# design.net
KiCad netlist of a schematic drawn in Altium Designer
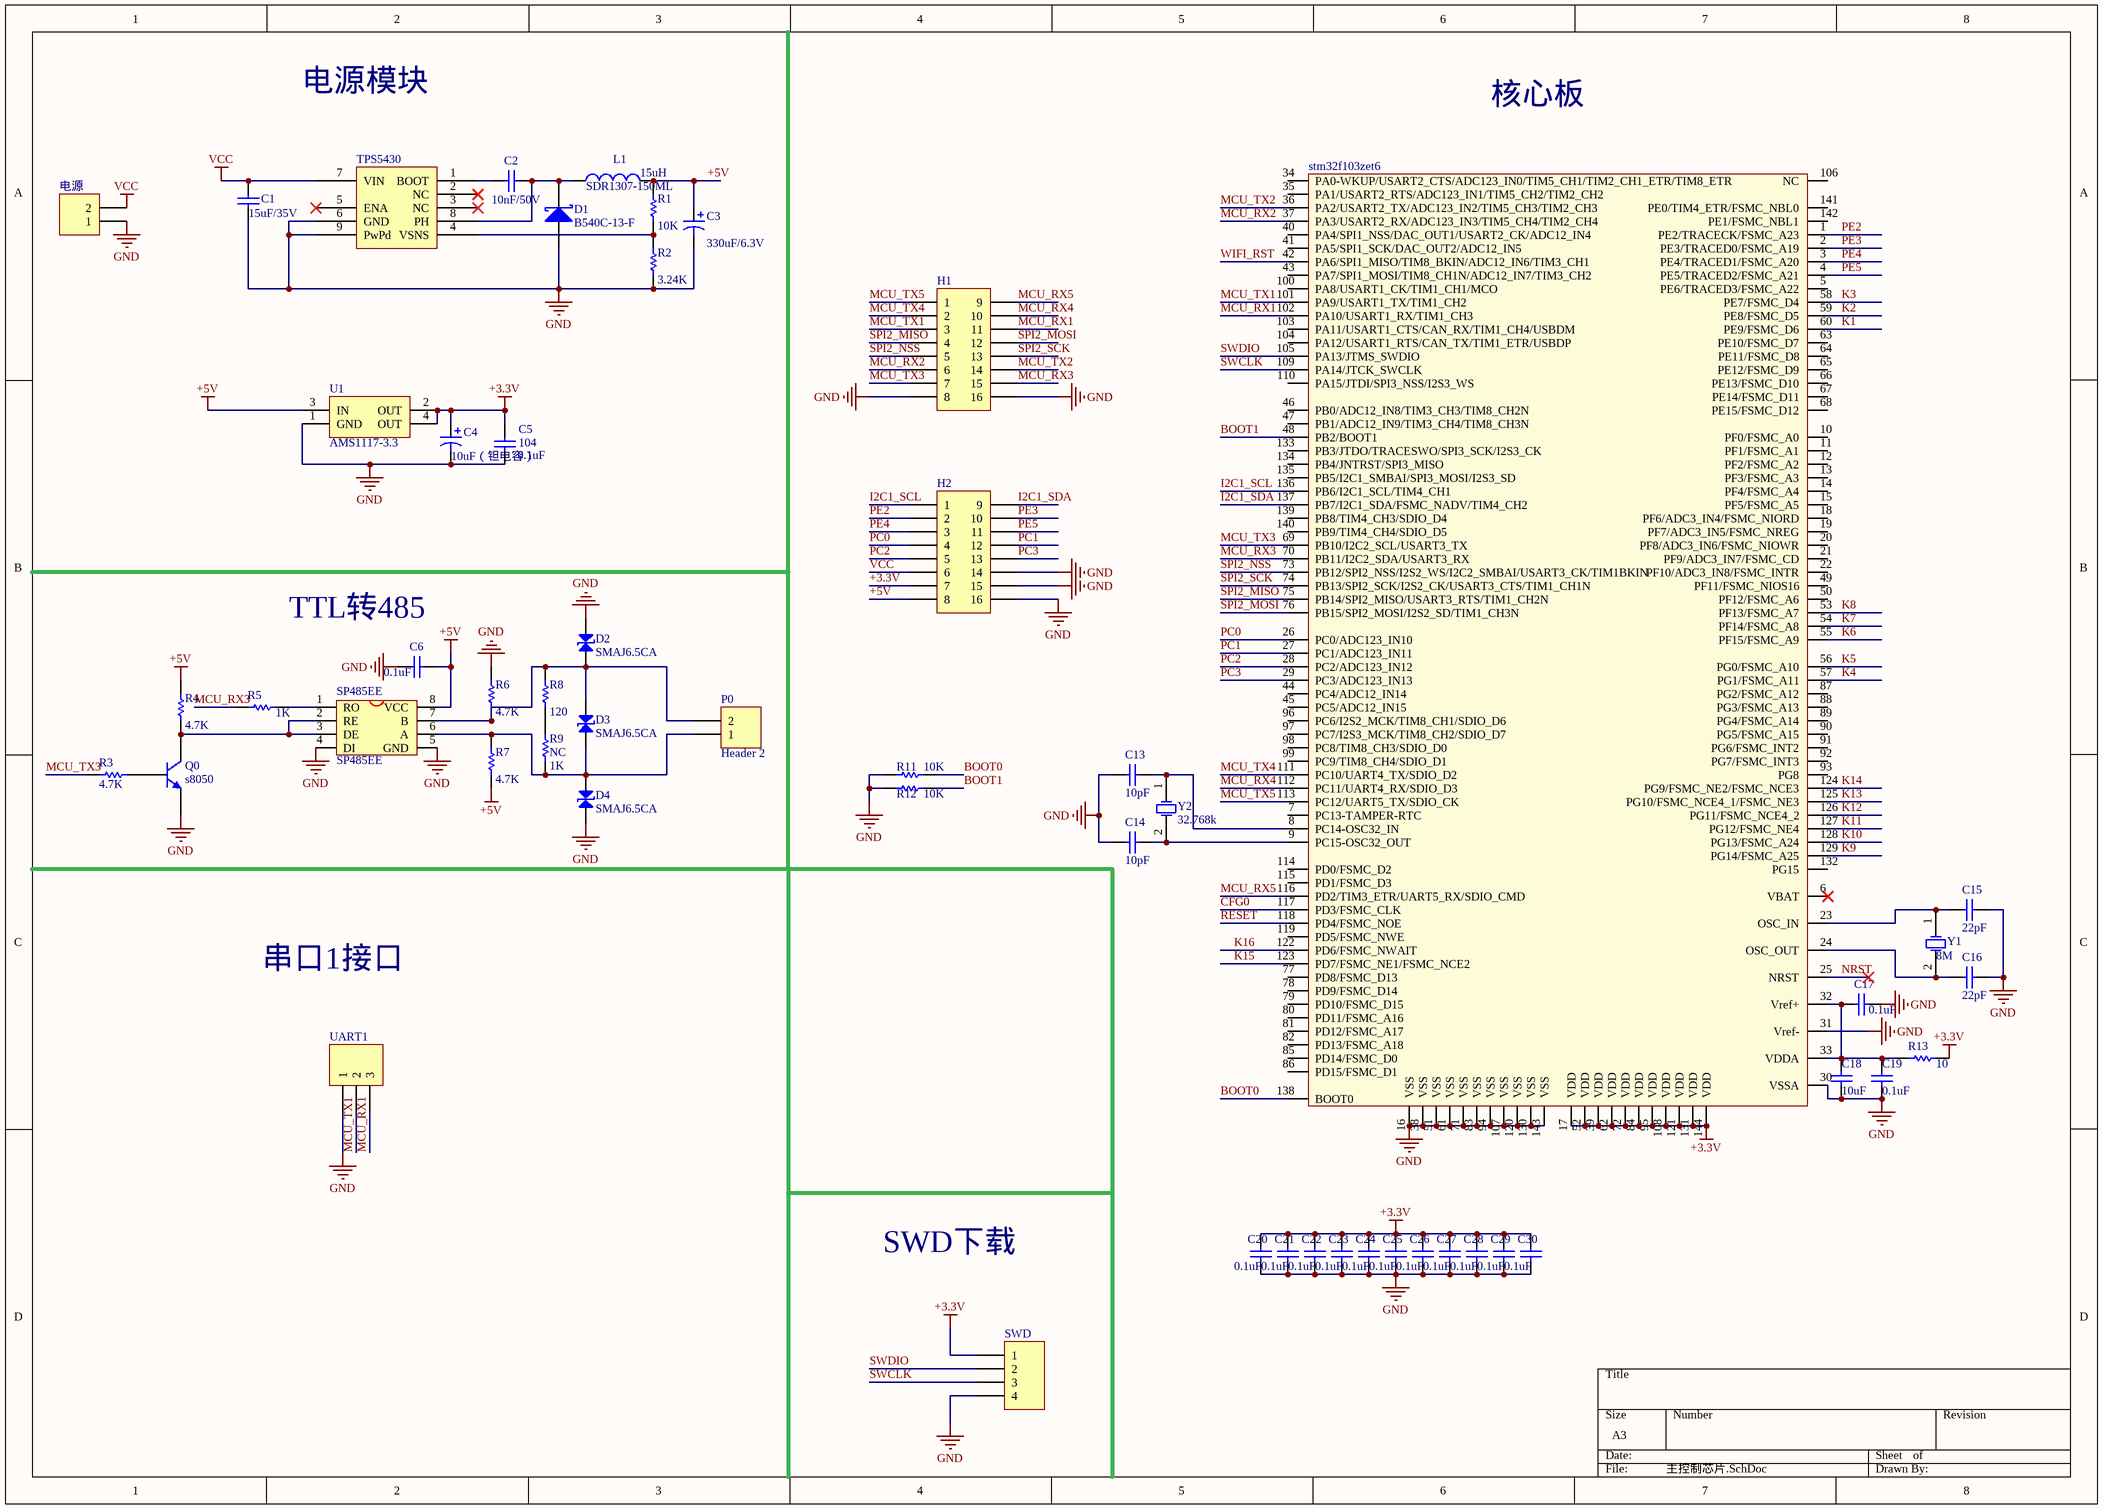
[diagram p0: 主控制芯片.SchDoc]

(export (version "E")
  (design (tool "Eeschema 10.0.6"))
  (components
    (comp (ref "C1")
      (value "15uF/35V")
      (footprint "1206")
      (description "Capacitor")
      (fields (field (name "Comment") "C2012X5R1V156M125AC") (field (name "PUBLISHER") "Altium Limited"))
      (libsource (lib "Miscellaneous Devices") (part "Cap"))
    )
    (comp (ref "C2")
      (value "10nF/50V")
      (footprint "0603")
      (description "Capacitor")
      (fields (field (name "Comment") "C0805C103K5RACTU") (field (name "PUBLISHER") "Altium Limited"))
      (libsource (lib "Miscellaneous Devices") (part "Cap"))
    )
    (comp (ref "C3")
      (value "330uF/6.3V")
      (footprint "钽电容(D)")
      (description "Polarized Capacitor (Radial)")
      (fields (field (name "Comment") "6TPC330MA") (field (name "PUBLISHER") "Altium Limited"))
      (libsource (lib "Miscellaneous Devices") (part "Cap Pol1"))
    )
    (comp (ref "C4")
      (value "10uF（钽电容）")
      (footprint "钽电容(B)")
      (description "Polarized Capacitor (Radial)")
      (fields (field (name "PUBLISHER") "Altium Limited"))
      (libsource (lib "Miscellaneous Devices") (part "Cap Pol1"))
    )
    (comp (ref "C5")
      (value "104")
      (footprint "0603")
      (description "Capacitor")
      (fields (field (name "ALTIUM_VALUE") "0.1uF") (field (name "PUBLISHER") "Altium Limited"))
      (libsource (lib "Miscellaneous Devices") (part "Cap"))
    )
    (comp (ref "C6")
      (value "0.1uF")
      (footprint "0603")
      (description "Capacitor")
      (fields (field (name "Comment") "104") (field (name "PUBLISHER") "Altium Limited"))
      (libsource (lib "Miscellaneous Devices") (part "Cap"))
    )
    (comp (ref "C13")
      (value "10pF")
      (footprint "0603")
      (description "Capacitor")
      (fields (field (name "Comment") "10") (field (name "PUBLISHER") "Altium Limited"))
      (libsource (lib "Miscellaneous Devices") (part "Cap"))
    )
    (comp (ref "C14")
      (value "10pF")
      (footprint "0603")
      (description "Capacitor")
      (fields (field (name "Comment") "10") (field (name "PUBLISHER") "Altium Limited"))
      (libsource (lib "Miscellaneous Devices") (part "Cap"))
    )
    (comp (ref "C15")
      (value "22pF")
      (footprint "0603")
      (description "Capacitor")
      (fields (field (name "Comment") "22") (field (name "PUBLISHER") "Altium Limited"))
      (libsource (lib "Miscellaneous Devices") (part "Cap"))
    )
    (comp (ref "C16")
      (value "22pF")
      (footprint "0603")
      (description "Capacitor")
      (fields (field (name "Comment") "22") (field (name "PUBLISHER") "Altium Limited"))
      (libsource (lib "Miscellaneous Devices") (part "Cap"))
    )
    (comp (ref "C17")
      (value "0.1uF")
      (footprint "0603")
      (description "Capacitor")
      (fields (field (name "Comment") "104") (field (name "PUBLISHER") "Altium Limited"))
      (libsource (lib "Miscellaneous Devices") (part "Cap"))
    )
    (comp (ref "C18")
      (value "10uF")
      (footprint "0603")
      (description "Capacitor")
      (fields (field (name "Comment") "106") (field (name "PUBLISHER") "Altium Limited"))
      (libsource (lib "Miscellaneous Devices") (part "Cap"))
    )
    (comp (ref "C19")
      (value "0.1uF")
      (footprint "0603")
      (description "Capacitor")
      (fields (field (name "Comment") "104") (field (name "PUBLISHER") "Altium Limited"))
      (libsource (lib "Miscellaneous Devices") (part "Cap"))
    )
    (comp (ref "C20")
      (value "0.1uF")
      (footprint "0603")
      (description "Capacitor")
      (fields (field (name "Comment") "104") (field (name "PUBLISHER") "Altium Limited"))
      (libsource (lib "Miscellaneous Devices") (part "Cap"))
    )
    (comp (ref "C21")
      (value "0.1uF")
      (footprint "0603")
      (description "Capacitor")
      (fields (field (name "Comment") "104") (field (name "PUBLISHER") "Altium Limited"))
      (libsource (lib "Miscellaneous Devices") (part "Cap"))
    )
    (comp (ref "C22")
      (value "0.1uF")
      (footprint "0603")
      (description "Capacitor")
      (fields (field (name "Comment") "104") (field (name "PUBLISHER") "Altium Limited"))
      (libsource (lib "Miscellaneous Devices") (part "Cap"))
    )
    (comp (ref "C23")
      (value "0.1uF")
      (footprint "0603")
      (description "Capacitor")
      (fields (field (name "Comment") "104") (field (name "PUBLISHER") "Altium Limited"))
      (libsource (lib "Miscellaneous Devices") (part "Cap"))
    )
    (comp (ref "C24")
      (value "0.1uF")
      (footprint "0603")
      (description "Capacitor")
      (fields (field (name "Comment") "104") (field (name "PUBLISHER") "Altium Limited"))
      (libsource (lib "Miscellaneous Devices") (part "Cap"))
    )
    (comp (ref "C25")
      (value "0.1uF")
      (footprint "0603")
      (description "Capacitor")
      (fields (field (name "Comment") "104") (field (name "PUBLISHER") "Altium Limited"))
      (libsource (lib "Miscellaneous Devices") (part "Cap"))
    )
    (comp (ref "C26")
      (value "0.1uF")
      (footprint "0603")
      (description "Capacitor")
      (fields (field (name "Comment") "104") (field (name "PUBLISHER") "Altium Limited"))
      (libsource (lib "Miscellaneous Devices") (part "Cap"))
    )
    (comp (ref "C27")
      (value "0.1uF")
      (footprint "0603")
      (description "Capacitor")
      (fields (field (name "Comment") "104") (field (name "PUBLISHER") "Altium Limited"))
      (libsource (lib "Miscellaneous Devices") (part "Cap"))
    )
    (comp (ref "C28")
      (value "0.1uF")
      (footprint "0603")
      (description "Capacitor")
      (fields (field (name "Comment") "104") (field (name "PUBLISHER") "Altium Limited"))
      (libsource (lib "Miscellaneous Devices") (part "Cap"))
    )
    (comp (ref "C29")
      (value "0.1uF")
      (footprint "0603")
      (description "Capacitor")
      (fields (field (name "Comment") "104") (field (name "PUBLISHER") "Altium Limited"))
      (libsource (lib "Miscellaneous Devices") (part "Cap"))
    )
    (comp (ref "C30")
      (value "0.1uF")
      (footprint "0603")
      (description "Capacitor")
      (fields (field (name "Comment") "104") (field (name "PUBLISHER") "Altium Limited"))
      (libsource (lib "Miscellaneous Devices") (part "Cap"))
    )
    (comp (ref "D1")
      (value "B540C-13-F")
      (footprint "SMC")
      (description "Schottky Diode")
      (fields (field (name "PUBLISHER") "Altium Limited"))
      (libsource (lib "Miscellaneous Devices") (part "D Schottky"))
    )
    (comp (ref "D2") (value "SMAJ6.5CA") (footprint "SMA") (libsource (lib "智能柜") (part "MSCJ6.5CA")))
    (comp (ref "D3") (value "SMAJ6.5CA") (footprint "SMA") (libsource (lib "智能柜") (part "MSCJ6.5CA")))
    (comp (ref "D4") (value "SMAJ6.5CA") (footprint "SMA") (libsource (lib "智能柜") (part "MSCJ6.5CA")))
    (comp (ref "H1")
      (value "Header 8X2A")
      (footprint "HDR2X8_CEN")
      (description "Header, 8-Pin, Dual row")
      (fields (field (name "PUBLISHER") "Altium Limited"))
      (libsource (lib "Miscellaneous Connectors") (part "Header 8X2A"))
    )
    (comp (ref "H2")
      (value "Header 8X2A")
      (footprint "HDR2X8_CEN")
      (description "Header, 8-Pin, Dual row")
      (fields (field (name "PUBLISHER") "Altium Limited"))
      (libsource (lib "Miscellaneous Connectors") (part "Header 8X2A"))
    )
    (comp (ref "L1")
      (value "SDR1307-150ML")
      (footprint "CDRH127")
      (description "Inductor")
      (fields (field (name "ALTIUM_VALUE") "15uH") (field (name "PUBLISHER") "Altium Limited"))
      (libsource (lib "Miscellaneous Devices") (part "Inductor"))
    )
    (comp (ref "P0")
      (value "Header 2")
      (footprint "电源")
      (description "Header, 2-Pin")
      (fields (field (name "PUBLISHER") "Altium Limited"))
      (libsource (lib "") (part "Header 2_1"))
    )
    (comp (ref "Q0")
      (value "s8050")
      (footprint "SOT-23")
      (description "NPN Bipolar Transistor")
      (fields (field (name "PUBLISHER") "Altium Limited"))
      (libsource (lib "Miscellaneous Devices") (part "NPN"))
    )
    (comp (ref "R1")
      (value "10K")
      (footprint "0603")
      (description "Resistor")
      (fields (field (name "PUBLISHER") "Altium Limited"))
      (libsource (lib "Miscellaneous Devices") (part "Res1"))
    )
    (comp (ref "R2")
      (value "3.24K")
      (footprint "0603")
      (description "Resistor")
      (fields (field (name "PUBLISHER") "Altium Limited"))
      (libsource (lib "Miscellaneous Devices") (part "Res1"))
    )
    (comp (ref "R3")
      (value "4.7K")
      (footprint "0603")
      (description "Resistor")
      (fields (field (name "Comment") "4.7k") (field (name "PUBLISHER") "Altium Limited"))
      (libsource (lib "Miscellaneous Devices") (part "Res1"))
    )
    (comp (ref "R4")
      (value "4.7K")
      (footprint "0603")
      (description "Resistor")
      (fields (field (name "Comment") "4.7k") (field (name "PUBLISHER") "Altium Limited"))
      (libsource (lib "Miscellaneous Devices") (part "Res1"))
    )
    (comp (ref "R5")
      (value "1K")
      (footprint "0603")
      (description "Resistor")
      (fields (field (name "PUBLISHER") "Altium Limited"))
      (libsource (lib "Miscellaneous Devices") (part "Res1"))
    )
    (comp (ref "R6")
      (value "4.7K")
      (footprint "0603")
      (description "Resistor")
      (fields (field (name "Comment") "4.7k") (field (name "PUBLISHER") "Altium Limited"))
      (libsource (lib "Miscellaneous Devices") (part "Res1"))
    )
    (comp (ref "R7")
      (value "4.7K")
      (footprint "0603")
      (description "Resistor")
      (fields (field (name "Comment") "4.7k") (field (name "PUBLISHER") "Altium Limited"))
      (libsource (lib "Miscellaneous Devices") (part "Res1"))
    )
    (comp (ref "R8")
      (value "120")
      (footprint "0603")
      (description "Resistor")
      (fields (field (name "PUBLISHER") "Altium Limited"))
      (libsource (lib "Miscellaneous Devices") (part "Res1"))
    )
    (comp (ref "R9")
      (value "NC")
      (footprint "0603")
      (description "Resistor")
      (fields (field (name "ALTIUM_VALUE") "1K") (field (name "PUBLISHER") "Altium Limited"))
      (libsource (lib "Miscellaneous Devices") (part "Res1"))
    )
    (comp (ref "R11")
      (value "10K")
      (footprint "0603")
      (description "Resistor")
      (fields (field (name "PUBLISHER") "Altium Limited"))
      (libsource (lib "Miscellaneous Devices") (part "Res1"))
    )
    (comp (ref "R12")
      (value "10K")
      (footprint "0603")
      (description "Resistor")
      (fields (field (name "PUBLISHER") "Altium Limited"))
      (libsource (lib "Miscellaneous Devices") (part "Res1"))
    )
    (comp (ref "R13")
      (value "10")
      (footprint "0603")
      (description "Resistor")
      (fields (field (name "PUBLISHER") "Altium Limited"))
      (libsource (lib "Miscellaneous Devices") (part "Res1"))
    )
    (comp (ref "SP485EE") (value "SP485EE") (footprint "SOP-8") (libsource (lib "智能柜") (part "SP485EE")))
    (comp (ref "stm32f103zet6")
      (value "stm32f103zet6")
      (footprint "LQFP144")
      (libsource (lib "智能柜") (part "stm32f103zet6"))
    )
    (comp (ref "SWD")
      (value "Header 4")
      (footprint "SWD")
      (description "Header, 4-Pin")
      (fields (field (name "PUBLISHER") "Altium Limited"))
      (libsource (lib "Miscellaneous Connectors") (part "Header 4"))
    )
    (comp (ref "TPS5430")
      (value "TPS5430DDAR")
      (footprint "TPS5430")
      (libsource (lib "Schlib1") (part "TPS5430"))
    )
    (comp (ref "U1")
      (value "AMS1117-3.3")
      (footprint "1117-3.3")
      (description "800mA and 1A Low Dropout Positive Regulator 2.85V, 3.3V, 5V, and Adjustable")
      (fields (field (name "PUBLISHER") "Altium Limited"))
      (libsource (lib "BB Power Mgt Voltage Regulator") (part "REG1117-3.3"))
    )
    (comp (ref "UART1")
      (value "Header 3")
      (footprint "H3")
      (description "Header, 3-Pin")
      (fields (field (name "PUBLISHER") "Altium Limited"))
      (libsource (lib "Miscellaneous Connectors") (part "Header 3"))
    )
    (comp (ref "Y1")
      (value "8M")
      (footprint "5032(8M)")
      (description "Crystal Oscillator")
      (fields (field (name "PUBLISHER") "Altium Limited"))
      (libsource (lib "Miscellaneous Devices") (part "XTAL"))
    )
    (comp (ref "Y2")
      (value "32.768k")
      (footprint "FC135(32.768K)")
      (description "Crystal Oscillator")
      (fields (field (name "PUBLISHER") "Altium Limited"))
      (libsource (lib "Miscellaneous Devices") (part "XTAL"))
    )
    (comp (ref "电源")
      (value "DUANZI")
      (footprint "电源")
      (description "Header, 2-Pin")
      (fields (field (name "PUBLISHER") "Altium Limited"))
      (libsource (lib "Miscellaneous Connectors") (part "Header 2"))
    )
  )
  (nets
    (net (code "1") (name "+3.3V") (class "Default")
      (node (ref "C20") (pin "1") (pinfunction "1_1") (pintype "passive"))
      (node (ref "C21") (pin "1") (pinfunction "1_1") (pintype "passive"))
      (node (ref "C22") (pin "1") (pinfunction "1_1") (pintype "passive"))
      (node (ref "C23") (pin "1") (pinfunction "1_1") (pintype "passive"))
      (node (ref "C24") (pin "1") (pinfunction "1_1") (pintype "passive"))
      (node (ref "C25") (pin "1") (pinfunction "1_1") (pintype "passive"))
      (node (ref "C26") (pin "1") (pinfunction "1_1") (pintype "passive"))
      (node (ref "C27") (pin "1") (pinfunction "1_1") (pintype "passive"))
      (node (ref "C28") (pin "1") (pinfunction "1_1") (pintype "passive"))
      (node (ref "C29") (pin "1") (pinfunction "1_1") (pintype "passive"))
      (node (ref "C30") (pin "1") (pinfunction "1_1") (pintype "passive"))
      (node (ref "C4") (pin "1") (pinfunction "1_1") (pintype "passive"))
      (node (ref "C5") (pin "2") (pinfunction "2_2") (pintype "passive"))
      (node (ref "H2") (pin "7") (pinfunction "7_7") (pintype "passive"))
      (node (ref "R13") (pin "2") (pinfunction "2_2") (pintype "passive"))
      (node (ref "SWD") (pin "1") (pinfunction "1_1") (pintype "passive"))
      (node (ref "U1") (pin "2") (pinfunction "OUT_2") (pintype "power_in"))
      (node (ref "U1") (pin "4") (pinfunction "OUT_4") (pintype "power_in"))
      (node (ref "stm32f103zet6") (pin "108") (pinfunction "VDD_108") (pintype "passive"))
      (node (ref "stm32f103zet6") (pin "121") (pinfunction "VDD_121") (pintype "passive"))
      (node (ref "stm32f103zet6") (pin "131") (pinfunction "VDD_131") (pintype "passive"))
      (node (ref "stm32f103zet6") (pin "144") (pinfunction "VDD_144") (pintype "passive"))
      (node (ref "stm32f103zet6") (pin "17") (pinfunction "VDD_17") (pintype "passive"))
      (node (ref "stm32f103zet6") (pin "39") (pinfunction "VDD_39") (pintype "passive"))
      (node (ref "stm32f103zet6") (pin "52") (pinfunction "VDD_52") (pintype "passive"))
      (node (ref "stm32f103zet6") (pin "62") (pinfunction "VDD_62") (pintype "passive"))
      (node (ref "stm32f103zet6") (pin "72") (pinfunction "VDD_72") (pintype "passive"))
      (node (ref "stm32f103zet6") (pin "84") (pinfunction "VDD_84") (pintype "passive"))
      (node (ref "stm32f103zet6") (pin "95") (pinfunction "VDD_95") (pintype "passive"))
    )
    (net (code "2") (name "+5V") (class "Default")
      (node (ref "C3") (pin "1") (pinfunction "1_1") (pintype "passive"))
      (node (ref "C6") (pin "2") (pinfunction "2_2") (pintype "passive"))
      (node (ref "H2") (pin "8") (pinfunction "8_8") (pintype "passive"))
      (node (ref "L1") (pin "2") (pinfunction "2_2") (pintype "passive"))
      (node (ref "R1") (pin "2") (pinfunction "2_2") (pintype "passive"))
      (node (ref "R4") (pin "1") (pinfunction "1_1") (pintype "passive"))
      (node (ref "R7") (pin "2") (pinfunction "2_2") (pintype "passive"))
      (node (ref "SP485EE") (pin "8") (pinfunction "VCC_8") (pintype "passive"))
      (node (ref "U1") (pin "3") (pinfunction "IN_3") (pintype "power_in"))
    )
    (net (code "3") (name "/BOOT0") (class "Default")
      (node (ref "R11") (pin "1") (pinfunction "1_1") (pintype "passive"))
      (node (ref "stm32f103zet6") (pin "138") (pinfunction "BOOT0_138") (pintype "passive"))
    )
    (net (code "4") (name "/BOOT1") (class "Default")
      (node (ref "R12") (pin "1") (pinfunction "1_1") (pintype "passive"))
      (node (ref "stm32f103zet6") (pin "48") (pinfunction "PB2/BOOT1_48") (pintype "passive"))
    )
    (net (code "5") (name "/CFG0") (class "Default")
      (node (ref "stm32f103zet6") (pin "117") (pinfunction "PD3/FSMC_CLK_117") (pintype "passive"))
    )
    (net (code "6") (name "/I2C1_SCL") (class "Default")
      (node (ref "H2") (pin "1") (pinfunction "1_1") (pintype "passive"))
      (node (ref "stm32f103zet6") (pin "136") (pinfunction "PB6/I2C1_SCL/TIM4_CH1_136") (pintype "passive"))
    )
    (net (code "7") (name "/I2C1_SDA") (class "Default")
      (node (ref "H2") (pin "9") (pinfunction "9_9") (pintype "passive"))
      (node (ref "stm32f103zet6") (pin "137") (pinfunction "PB7/I2C1_SDA/FSMC_NADV/TIM4_CH2_137") (pintype "passive"))
    )
    (net (code "8") (name "/K1") (class "Default")
      (node (ref "stm32f103zet6") (pin "60") (pinfunction "PE9/FSMC_D6_60") (pintype "passive"))
    )
    (net (code "9") (name "/K2") (class "Default")
      (node (ref "stm32f103zet6") (pin "59") (pinfunction "PE8/FSMC_D5_59") (pintype "passive"))
    )
    (net (code "10") (name "/K3") (class "Default")
      (node (ref "stm32f103zet6") (pin "58") (pinfunction "PE7/FSMC_D4_58") (pintype "passive"))
    )
    (net (code "11") (name "/K4") (class "Default")
      (node (ref "stm32f103zet6") (pin "57") (pinfunction "PG1/FSMC_A11_57") (pintype "passive"))
    )
    (net (code "12") (name "/K5") (class "Default")
      (node (ref "stm32f103zet6") (pin "56") (pinfunction "PG0/FSMC_A10_56") (pintype "passive"))
    )
    (net (code "13") (name "/K6") (class "Default")
      (node (ref "stm32f103zet6") (pin "55") (pinfunction "PF15/FSMC_A9_55") (pintype "passive"))
    )
    (net (code "14") (name "/K7") (class "Default")
      (node (ref "stm32f103zet6") (pin "54") (pinfunction "PF14/FSMC_A8_54") (pintype "passive"))
    )
    (net (code "15") (name "/K8") (class "Default")
      (node (ref "stm32f103zet6") (pin "53") (pinfunction "PF13/FSMC_A7_53") (pintype "passive"))
    )
    (net (code "16") (name "/K9") (class "Default")
      (node (ref "stm32f103zet6") (pin "129") (pinfunction "PG14/FSMC_A25_129") (pintype "passive"))
    )
    (net (code "17") (name "/K10") (class "Default")
      (node (ref "stm32f103zet6") (pin "128") (pinfunction "PG13/FSMC_A24_128") (pintype "passive"))
    )
    (net (code "18") (name "/K11") (class "Default")
      (node (ref "stm32f103zet6") (pin "127") (pinfunction "PG12/FSMC_NE4_127") (pintype "passive"))
    )
    (net (code "19") (name "/K12") (class "Default")
      (node (ref "stm32f103zet6") (pin "126") (pinfunction "PG11/FSMC_NCE4_2_126") (pintype "passive"))
    )
    (net (code "20") (name "/K13") (class "Default")
      (node (ref "stm32f103zet6") (pin "125") (pinfunction "PG10/FSMC_NCE4_1/FSMC_NE3_125") (pintype "passive"))
    )
    (net (code "21") (name "/K14") (class "Default")
      (node (ref "stm32f103zet6") (pin "124") (pinfunction "PG9/FSMC_NE2/FSMC_NCE3_124") (pintype "passive"))
    )
    (net (code "22") (name "/K15") (class "Default")
      (node (ref "stm32f103zet6") (pin "123") (pinfunction "PD7/FSMC_NE1/FSMC_NCE2_123") (pintype "passive"))
    )
    (net (code "23") (name "/K16") (class "Default")
      (node (ref "stm32f103zet6") (pin "122") (pinfunction "PD6/FSMC_NWAIT_122") (pintype "passive"))
    )
    (net (code "24") (name "/MCU_RX1") (class "Default")
      (node (ref "H1") (pin "11") (pinfunction "11_11") (pintype "passive"))
      (node (ref "UART1") (pin "3") (pinfunction "3_3") (pintype "passive"))
      (node (ref "stm32f103zet6") (pin "102") (pinfunction "PA10/USART1_RX/TIM1_CH3_102") (pintype "passive"))
    )
    (net (code "25") (name "/MCU_RX2") (class "Default")
      (node (ref "H1") (pin "6") (pinfunction "6_6") (pintype "passive"))
      (node (ref "stm32f103zet6") (pin "37") (pinfunction "PA3/USART2_RX/ADC123_IN3/TIM5_CH4/TIM2_CH4_37") (pintype "passive"))
    )
    (net (code "26") (name "/MCU_RX3") (class "Default")
      (node (ref "H1") (pin "15") (pinfunction "15_15") (pintype "passive"))
      (node (ref "R5") (pin "1") (pinfunction "1_1") (pintype "passive"))
      (node (ref "stm32f103zet6") (pin "70") (pinfunction "PB11/I2C2_SDA/USART3_RX_70") (pintype "passive"))
    )
    (net (code "27") (name "/MCU_RX4") (class "Default")
      (node (ref "H1") (pin "10") (pinfunction "10_10") (pintype "passive"))
      (node (ref "stm32f103zet6") (pin "112") (pinfunction "PC11/UART4_RX/SDIO_D3_112") (pintype "passive"))
    )
    (net (code "28") (name "/MCU_RX5") (class "Default")
      (node (ref "H1") (pin "9") (pinfunction "9_9") (pintype "passive"))
      (node (ref "stm32f103zet6") (pin "116") (pinfunction "PD2/TIM3_ETR/UART5_RX/SDIO_CMD_116") (pintype "passive"))
    )
    (net (code "29") (name "/MCU_TX1") (class "Default")
      (node (ref "H1") (pin "3") (pinfunction "3_3") (pintype "passive"))
      (node (ref "UART1") (pin "2") (pinfunction "2_2") (pintype "passive"))
      (node (ref "stm32f103zet6") (pin "101") (pinfunction "PA9/USART1_TX/TIM1_CH2_101") (pintype "passive"))
    )
    (net (code "30") (name "/MCU_TX2") (class "Default")
      (node (ref "H1") (pin "14") (pinfunction "14_14") (pintype "passive"))
      (node (ref "stm32f103zet6") (pin "36") (pinfunction "PA2/USART2_TX/ADC123_IN2/TIM5_CH3/TIM2_CH3_36") (pintype "passive"))
    )
    (net (code "31") (name "/MCU_TX3") (class "Default")
      (node (ref "H1") (pin "7") (pinfunction "7_7") (pintype "passive"))
      (node (ref "R3") (pin "1") (pinfunction "1_1") (pintype "passive"))
      (node (ref "stm32f103zet6") (pin "69") (pinfunction "PB10/I2C2_SCL/USART3_TX_69") (pintype "passive"))
    )
    (net (code "32") (name "/MCU_TX4") (class "Default")
      (node (ref "H1") (pin "2") (pinfunction "2_2") (pintype "passive"))
      (node (ref "stm32f103zet6") (pin "111") (pinfunction "PC10/UART4_TX/SDIO_D2_111") (pintype "passive"))
    )
    (net (code "33") (name "/MCU_TX5") (class "Default")
      (node (ref "H1") (pin "1") (pinfunction "1_1") (pintype "passive"))
      (node (ref "stm32f103zet6") (pin "113") (pinfunction "PC12/UART5_TX/SDIO_CK_113") (pintype "passive"))
    )
    (net (code "34") (name "/NRST") (class "Default")
      (node (ref "stm32f103zet6") (pin "25") (pinfunction "NRST_25") (pintype "passive+no_connect"))
    )
    (net (code "35") (name "/PC0") (class "Default")
      (node (ref "H2") (pin "4") (pinfunction "4_4") (pintype "passive"))
      (node (ref "stm32f103zet6") (pin "26") (pinfunction "PC0/ADC123_IN10_26") (pintype "passive"))
    )
    (net (code "36") (name "/PC1") (class "Default")
      (node (ref "H2") (pin "12") (pinfunction "12_12") (pintype "passive"))
      (node (ref "stm32f103zet6") (pin "27") (pinfunction "PC1/ADC123_IN11_27") (pintype "passive"))
    )
    (net (code "37") (name "/PC2") (class "Default")
      (node (ref "H2") (pin "5") (pinfunction "5_5") (pintype "passive"))
      (node (ref "stm32f103zet6") (pin "28") (pinfunction "PC2/ADC123_IN12_28") (pintype "passive"))
    )
    (net (code "38") (name "/PC3") (class "Default")
      (node (ref "H2") (pin "13") (pinfunction "13_13") (pintype "passive"))
      (node (ref "stm32f103zet6") (pin "29") (pinfunction "PC3/ADC123_IN13_29") (pintype "passive"))
    )
    (net (code "39") (name "/PE2") (class "Default")
      (node (ref "H2") (pin "2") (pinfunction "2_2") (pintype "passive"))
      (node (ref "stm32f103zet6") (pin "1") (pinfunction "PE2/TRACECK/FSMC_A23_1") (pintype "passive"))
    )
    (net (code "40") (name "/PE3") (class "Default")
      (node (ref "H2") (pin "10") (pinfunction "10_10") (pintype "passive"))
      (node (ref "stm32f103zet6") (pin "2") (pinfunction "PE3/TRACED0/FSMC_A19_2") (pintype "passive"))
    )
    (net (code "41") (name "/PE4") (class "Default")
      (node (ref "H2") (pin "3") (pinfunction "3_3") (pintype "passive"))
      (node (ref "stm32f103zet6") (pin "3") (pinfunction "PE4/TRACED1/FSMC_A20_3") (pintype "passive"))
    )
    (net (code "42") (name "/PE5") (class "Default")
      (node (ref "H2") (pin "11") (pinfunction "11_11") (pintype "passive"))
      (node (ref "stm32f103zet6") (pin "4") (pinfunction "PE5/TRACED2/FSMC_A21_4") (pintype "passive"))
    )
    (net (code "43") (name "/RESET") (class "Default")
      (node (ref "stm32f103zet6") (pin "118") (pinfunction "PD4/FSMC_NOE_118") (pintype "passive"))
    )
    (net (code "44") (name "/SPI2_MISO") (class "Default")
      (node (ref "H1") (pin "4") (pinfunction "4_4") (pintype "passive"))
      (node (ref "stm32f103zet6") (pin "75") (pinfunction "PB14/SPI2_MISO/USART3_RTS/TIM1_CH2N_75") (pintype "passive"))
    )
    (net (code "45") (name "/SPI2_MOSI") (class "Default")
      (node (ref "H1") (pin "12") (pinfunction "12_12") (pintype "passive"))
      (node (ref "stm32f103zet6") (pin "76") (pinfunction "PB15/SPI2_MOSI/I2S2_SD/TIM1_CH3N_76") (pintype "passive"))
    )
    (net (code "46") (name "/SPI2_NSS") (class "Default")
      (node (ref "H1") (pin "5") (pinfunction "5_5") (pintype "passive"))
      (node (ref "stm32f103zet6") (pin "73") (pinfunction "PB12/SPI2_NSS/I2S2_WS/I2C2_SMBAI/USART3_CK/TIM1BKIN_73") (pintype "passive"))
    )
    (net (code "47") (name "/SPI2_SCK") (class "Default")
      (node (ref "H1") (pin "13") (pinfunction "13_13") (pintype "passive"))
      (node (ref "stm32f103zet6") (pin "74") (pinfunction "PB13/SPI2_SCK/I2S2_CK/USART3_CTS/TIM1_CH1N_74") (pintype "passive"))
    )
    (net (code "48") (name "/SWCLK") (class "Default")
      (node (ref "SWD") (pin "3") (pinfunction "3_3") (pintype "passive"))
      (node (ref "stm32f103zet6") (pin "109") (pinfunction "PA14/JTCK_SWCLK_109") (pintype "passive"))
    )
    (net (code "49") (name "/SWDIO") (class "Default")
      (node (ref "SWD") (pin "2") (pinfunction "2_2") (pintype "passive"))
      (node (ref "stm32f103zet6") (pin "105") (pinfunction "PA13/JTMS_SWDIO_105") (pintype "passive"))
    )
    (net (code "50") (name "/WIFI_RST") (class "Default")
      (node (ref "stm32f103zet6") (pin "42") (pinfunction "PA6/SPI1_MISO/TIM8_BKIN/ADC12_IN6/TIM3_CH1_42") (pintype "passive"))
    )
    (net (code "51") (name "GND") (class "Default")
      (node (ref "C1") (pin "2") (pinfunction "2_2") (pintype "passive"))
      (node (ref "C13") (pin "2") (pinfunction "2_2") (pintype "passive"))
      (node (ref "C14") (pin "2") (pinfunction "2_2") (pintype "passive"))
      (node (ref "C15") (pin "1") (pinfunction "1_1") (pintype "passive"))
      (node (ref "C16") (pin "1") (pinfunction "1_1") (pintype "passive"))
      (node (ref "C17") (pin "1") (pinfunction "1_1") (pintype "passive"))
      (node (ref "C18") (pin "2") (pinfunction "2_2") (pintype "passive"))
      (node (ref "C19") (pin "2") (pinfunction "2_2") (pintype "passive"))
      (node (ref "C20") (pin "2") (pinfunction "2_2") (pintype "passive"))
      (node (ref "C21") (pin "2") (pinfunction "2_2") (pintype "passive"))
      (node (ref "C22") (pin "2") (pinfunction "2_2") (pintype "passive"))
      (node (ref "C23") (pin "2") (pinfunction "2_2") (pintype "passive"))
      (node (ref "C24") (pin "2") (pinfunction "2_2") (pintype "passive"))
      (node (ref "C25") (pin "2") (pinfunction "2_2") (pintype "passive"))
      (node (ref "C26") (pin "2") (pinfunction "2_2") (pintype "passive"))
      (node (ref "C27") (pin "2") (pinfunction "2_2") (pintype "passive"))
      (node (ref "C28") (pin "2") (pinfunction "2_2") (pintype "passive"))
      (node (ref "C29") (pin "2") (pinfunction "2_2") (pintype "passive"))
      (node (ref "C3") (pin "2") (pinfunction "2_2") (pintype "passive"))
      (node (ref "C30") (pin "2") (pinfunction "2_2") (pintype "passive"))
      (node (ref "C4") (pin "2") (pinfunction "2_2") (pintype "passive"))
      (node (ref "C5") (pin "1") (pinfunction "1_1") (pintype "passive"))
      (node (ref "C6") (pin "1") (pinfunction "1_1") (pintype "passive"))
      (node (ref "D1") (pin "1") (pinfunction "A_1") (pintype "passive"))
      (node (ref "D2") (pin "2") (pintype "passive"))
      (node (ref "D4") (pin "1") (pintype "passive"))
      (node (ref "H1") (pin "16") (pinfunction "16_16") (pintype "passive"))
      (node (ref "H1") (pin "8") (pinfunction "8_8") (pintype "passive"))
      (node (ref "H2") (pin "14") (pinfunction "14_14") (pintype "passive"))
      (node (ref "H2") (pin "15") (pinfunction "15_15") (pintype "passive"))
      (node (ref "H2") (pin "16") (pinfunction "16_16") (pintype "passive"))
      (node (ref "Q0") (pin "3") (pinfunction "E_3") (pintype "passive"))
      (node (ref "R11") (pin "2") (pinfunction "2_2") (pintype "passive"))
      (node (ref "R12") (pin "2") (pinfunction "2_2") (pintype "passive"))
      (node (ref "R2") (pin "1") (pinfunction "1_1") (pintype "passive"))
      (node (ref "R6") (pin "1") (pinfunction "1_1") (pintype "passive"))
      (node (ref "SP485EE") (pin "4") (pinfunction "DI_4") (pintype "passive"))
      (node (ref "SP485EE") (pin "5") (pinfunction "GND_5") (pintype "passive"))
      (node (ref "SWD") (pin "4") (pinfunction "4_4") (pintype "passive"))
      (node (ref "TPS5430") (pin "6") (pinfunction "GND_6") (pintype "passive"))
      (node (ref "TPS5430") (pin "9") (pinfunction "PwPd_9") (pintype "passive"))
      (node (ref "U1") (pin "1") (pinfunction "GND_1") (pintype "power_in"))
      (node (ref "UART1") (pin "1") (pinfunction "1_1") (pintype "passive"))
      (node (ref "stm32f103zet6") (pin "107") (pinfunction "VSS_107") (pintype "passive"))
      (node (ref "stm32f103zet6") (pin "120") (pinfunction "VSS_120") (pintype "passive"))
      (node (ref "stm32f103zet6") (pin "130") (pinfunction "VSS_130") (pintype "passive"))
      (node (ref "stm32f103zet6") (pin "143") (pinfunction "VSS_143") (pintype "passive"))
      (node (ref "stm32f103zet6") (pin "16") (pinfunction "VSS_16") (pintype "passive"))
      (node (ref "stm32f103zet6") (pin "30") (pinfunction "VSSA_30") (pintype "passive"))
      (node (ref "stm32f103zet6") (pin "31") (pinfunction "Vref-_31") (pintype "passive"))
      (node (ref "stm32f103zet6") (pin "38") (pinfunction "VSS_38") (pintype "passive"))
      (node (ref "stm32f103zet6") (pin "51") (pinfunction "VSS_51") (pintype "passive"))
      (node (ref "stm32f103zet6") (pin "61") (pinfunction "VSS_61") (pintype "passive"))
      (node (ref "stm32f103zet6") (pin "71") (pinfunction "VSS_71") (pintype "passive"))
      (node (ref "stm32f103zet6") (pin "83") (pinfunction "VSS_83") (pintype "passive"))
      (node (ref "stm32f103zet6") (pin "94") (pinfunction "VSS_94") (pintype "passive"))
      (node (ref "电源") (pin "1") (pinfunction "1_1") (pintype "passive"))
    )
    (net (code "52") (name "Net-(D1-K)") (class "Default")
      (node (ref "C2") (pin "2") (pinfunction "2_2") (pintype "passive"))
      (node (ref "D1") (pin "2") (pinfunction "K_2") (pintype "passive"))
      (node (ref "L1") (pin "1") (pinfunction "1_1") (pintype "passive"))
      (node (ref "TPS5430") (pin "8") (pinfunction "PH_8") (pintype "passive"))
    )
    (net (code "53") (name "Net-(Q0-B)") (class "Default")
      (node (ref "Q0") (pin "2") (pinfunction "B_2") (pintype "passive"))
      (node (ref "R3") (pin "2") (pinfunction "2_2") (pintype "passive"))
    )
    (net (code "54") (name "Net-(Q0-C)") (class "Default")
      (node (ref "Q0") (pin "1") (pinfunction "C_1") (pintype "passive"))
      (node (ref "R4") (pin "2") (pinfunction "2_2") (pintype "passive"))
      (node (ref "SP485EE") (pin "2") (pinfunction "RE_2") (pintype "passive"))
      (node (ref "SP485EE") (pin "3") (pinfunction "DE_3") (pintype "passive"))
    )
    (net (code "55") (name "Net-(R8-Pad1)") (class "Default")
      (node (ref "R8") (pin "1") (pinfunction "1_1") (pintype "passive"))
      (node (ref "R9") (pin "2") (pinfunction "2_2") (pintype "passive"))
    )
    (net (code "56") (name "Net-(SP485EE-A)") (class "Default")
      (node (ref "D3") (pin "1") (pintype "passive"))
      (node (ref "D4") (pin "2") (pintype "passive"))
      (node (ref "P0") (pin "1") (pinfunction "1_1") (pintype "passive"))
      (node (ref "R7") (pin "1") (pinfunction "1_1") (pintype "passive"))
      (node (ref "R9") (pin "1") (pinfunction "1_1") (pintype "passive"))
      (node (ref "SP485EE") (pin "6") (pinfunction "A_6") (pintype "passive"))
    )
    (net (code "57") (name "Net-(SP485EE-B)") (class "Default")
      (node (ref "D2") (pin "1") (pintype "passive"))
      (node (ref "D3") (pin "2") (pintype "passive"))
      (node (ref "P0") (pin "2") (pinfunction "2_2") (pintype "passive"))
      (node (ref "R6") (pin "2") (pinfunction "2_2") (pintype "passive"))
      (node (ref "R8") (pin "2") (pinfunction "2_2") (pintype "passive"))
      (node (ref "SP485EE") (pin "7") (pinfunction "B_7") (pintype "passive"))
    )
    (net (code "58") (name "Net-(SP485EE-RO)") (class "Default")
      (node (ref "R5") (pin "2") (pinfunction "2_2") (pintype "passive"))
      (node (ref "SP485EE") (pin "1") (pinfunction "RO_1") (pintype "passive"))
    )
    (net (code "59") (name "Net-(TPS5430-BOOT)") (class "Default")
      (node (ref "C2") (pin "1") (pinfunction "1_1") (pintype "passive"))
      (node (ref "TPS5430") (pin "1") (pinfunction "BOOT_1") (pintype "passive"))
    )
    (net (code "60") (name "Net-(TPS5430-VSNS)") (class "Default")
      (node (ref "R1") (pin "1") (pinfunction "1_1") (pintype "passive"))
      (node (ref "R2") (pin "2") (pinfunction "2_2") (pintype "passive"))
      (node (ref "TPS5430") (pin "4") (pinfunction "VSNS_4") (pintype "passive"))
    )
    (net (code "61") (name "Net-(Y1-OSC1)") (class "Default")
      (node (ref "C15") (pin "2") (pinfunction "2_2") (pintype "passive"))
      (node (ref "Y1") (pin "1") (pinfunction "OSC1_1") (pintype "passive"))
      (node (ref "stm32f103zet6") (pin "23") (pinfunction "OSC_IN_23") (pintype "passive"))
    )
    (net (code "62") (name "Net-(Y1-OSC2)") (class "Default")
      (node (ref "C16") (pin "2") (pinfunction "2_2") (pintype "passive"))
      (node (ref "Y1") (pin "2") (pinfunction "OSC2_2") (pintype "passive"))
      (node (ref "stm32f103zet6") (pin "24") (pinfunction "OSC_OUT_24") (pintype "passive"))
    )
    (net (code "63") (name "Net-(Y2-OSC1)") (class "Default")
      (node (ref "C13") (pin "1") (pinfunction "1_1") (pintype "passive"))
      (node (ref "Y2") (pin "1") (pinfunction "OSC1_1") (pintype "passive"))
      (node (ref "stm32f103zet6") (pin "8") (pinfunction "PC14-OSC32_IN_8") (pintype "passive"))
    )
    (net (code "64") (name "Net-(Y2-OSC2)") (class "Default")
      (node (ref "C14") (pin "1") (pinfunction "1_1") (pintype "passive"))
      (node (ref "Y2") (pin "2") (pinfunction "OSC2_2") (pintype "passive"))
      (node (ref "stm32f103zet6") (pin "9") (pinfunction "PC15-OSC32_OUT_9") (pintype "passive"))
    )
    (net (code "65") (name "Net-(stm32f103zet6-VDDA)") (class "Default")
      (node (ref "C17") (pin "2") (pinfunction "2_2") (pintype "passive"))
      (node (ref "C18") (pin "1") (pinfunction "1_1") (pintype "passive"))
      (node (ref "C19") (pin "1") (pinfunction "1_1") (pintype "passive"))
      (node (ref "R13") (pin "1") (pinfunction "1_1") (pintype "passive"))
      (node (ref "stm32f103zet6") (pin "32") (pinfunction "Vref+_32") (pintype "passive"))
      (node (ref "stm32f103zet6") (pin "33") (pinfunction "VDDA_33") (pintype "passive"))
    )
    (net (code "66") (name "VCC") (class "Default")
      (node (ref "C1") (pin "1") (pinfunction "1_1") (pintype "passive"))
      (node (ref "H2") (pin "6") (pinfunction "6_6") (pintype "passive"))
      (node (ref "TPS5430") (pin "7") (pinfunction "VIN_7") (pintype "passive"))
      (node (ref "电源") (pin "2") (pinfunction "2_2") (pintype "passive"))
    )
    (net (code "67") (name "unconnected-(TPS5430-ENA-Pad5)") (class "Default")
      (node (ref "TPS5430") (pin "5") (pinfunction "ENA_5") (pintype "passive+no_connect"))
    )
    (net (code "68") (name "unconnected-(TPS5430-NC-Pad2)") (class "Default")
      (node (ref "TPS5430") (pin "2") (pinfunction "NC_2") (pintype "passive+no_connect"))
    )
    (net (code "69") (name "unconnected-(TPS5430-NC-Pad3)") (class "Default")
      (node (ref "TPS5430") (pin "3") (pinfunction "NC_3") (pintype "passive+no_connect"))
    )
    (net (code "70") (name "unconnected-(stm32f103zet6-NC-Pad106)") (class "Default")
      (node (ref "stm32f103zet6") (pin "106") (pinfunction "NC_106") (pintype "passive"))
    )
    (net (code "71") (name "unconnected-(stm32f103zet6-PA0-WKUP{slash}USART2_CTS{slash}ADC123_IN0{slash}TIM5_CH1{slash}TIM2_CH1_ETR{slash}TIM8_ETR-Pad34)") (class "Default")
      (node (ref "stm32f103zet6") (pin "34") (pinfunction "PA0-WKUP/USART2_CTS/ADC123_IN0/TIM5_CH1/TIM2_CH1_ETR/TIM8_ETR_34") (pintype "passive"))
    )
    (net (code "72") (name "unconnected-(stm32f103zet6-PA1{slash}USART2_RTS{slash}ADC123_IN1{slash}TIM5_CH2{slash}TIM2_CH2-Pad35)") (class "Default")
      (node (ref "stm32f103zet6") (pin "35") (pinfunction "PA1/USART2_RTS/ADC123_IN1/TIM5_CH2/TIM2_CH2_35") (pintype "passive"))
    )
    (net (code "73") (name "unconnected-(stm32f103zet6-PA4{slash}SPI1_NSS{slash}DAC_OUT1{slash}USART2_CK{slash}ADC12_IN4-Pad40)") (class "Default")
      (node (ref "stm32f103zet6") (pin "40") (pinfunction "PA4/SPI1_NSS/DAC_OUT1/USART2_CK/ADC12_IN4_40") (pintype "passive"))
    )
    (net (code "74") (name "unconnected-(stm32f103zet6-PA5{slash}SPI1_SCK{slash}DAC_OUT2{slash}ADC12_IN5-Pad41)") (class "Default")
      (node (ref "stm32f103zet6") (pin "41") (pinfunction "PA5/SPI1_SCK/DAC_OUT2/ADC12_IN5_41") (pintype "passive"))
    )
    (net (code "75") (name "unconnected-(stm32f103zet6-PA7{slash}SPI1_MOSI{slash}TIM8_CH1N{slash}ADC12_IN7{slash}TIM3_CH2-Pad43)") (class "Default")
      (node (ref "stm32f103zet6") (pin "43") (pinfunction "PA7/SPI1_MOSI/TIM8_CH1N/ADC12_IN7/TIM3_CH2_43") (pintype "passive"))
    )
    (net (code "76") (name "unconnected-(stm32f103zet6-PA8{slash}USART1_CK{slash}TIM1_CH1{slash}MCO-Pad100)") (class "Default")
      (node (ref "stm32f103zet6") (pin "100") (pinfunction "PA8/USART1_CK/TIM1_CH1/MCO_100") (pintype "passive"))
    )
    (net (code "77") (name "unconnected-(stm32f103zet6-PA11{slash}USART1_CTS{slash}CAN_RX{slash}TIM1_CH4{slash}USBDM-Pad103)") (class "Default")
      (node (ref "stm32f103zet6") (pin "103") (pinfunction "PA11/USART1_CTS/CAN_RX/TIM1_CH4/USBDM_103") (pintype "passive"))
    )
    (net (code "78") (name "unconnected-(stm32f103zet6-PA12{slash}USART1_RTS{slash}CAN_TX{slash}TIM1_ETR{slash}USBDP-Pad104)") (class "Default")
      (node (ref "stm32f103zet6") (pin "104") (pinfunction "PA12/USART1_RTS/CAN_TX/TIM1_ETR/USBDP_104") (pintype "passive"))
    )
    (net (code "79") (name "unconnected-(stm32f103zet6-PA15{slash}JTDI{slash}SPI3_NSS{slash}I2S3_WS-Pad110)") (class "Default")
      (node (ref "stm32f103zet6") (pin "110") (pinfunction "PA15/JTDI/SPI3_NSS/I2S3_WS_110") (pintype "passive"))
    )
    (net (code "80") (name "unconnected-(stm32f103zet6-PB0{slash}ADC12_IN8{slash}TIM3_CH3{slash}TIM8_CH2N-Pad46)") (class "Default")
      (node (ref "stm32f103zet6") (pin "46") (pinfunction "PB0/ADC12_IN8/TIM3_CH3/TIM8_CH2N_46") (pintype "passive"))
    )
    (net (code "81") (name "unconnected-(stm32f103zet6-PB1{slash}ADC12_IN9{slash}TIM3_CH4{slash}TIM8_CH3N-Pad47)") (class "Default")
      (node (ref "stm32f103zet6") (pin "47") (pinfunction "PB1/ADC12_IN9/TIM3_CH4/TIM8_CH3N_47") (pintype "passive"))
    )
    (net (code "82") (name "unconnected-(stm32f103zet6-PB3{slash}JTDO{slash}TRACESWO{slash}SPI3_SCK{slash}I2S3_CK-Pad133)") (class "Default")
      (node (ref "stm32f103zet6") (pin "133") (pinfunction "PB3/JTDO/TRACESWO/SPI3_SCK/I2S3_CK_133") (pintype "passive"))
    )
    (net (code "83") (name "unconnected-(stm32f103zet6-PB4{slash}JNTRST{slash}SPI3_MISO-Pad134)") (class "Default")
      (node (ref "stm32f103zet6") (pin "134") (pinfunction "PB4/JNTRST/SPI3_MISO_134") (pintype "passive"))
    )
    (net (code "84") (name "unconnected-(stm32f103zet6-PB5{slash}I2C1_SMBAI{slash}SPI3_MOSI{slash}I2S3_SD-Pad135)") (class "Default")
      (node (ref "stm32f103zet6") (pin "135") (pinfunction "PB5/I2C1_SMBAI/SPI3_MOSI/I2S3_SD_135") (pintype "passive"))
    )
    (net (code "85") (name "unconnected-(stm32f103zet6-PB8{slash}TIM4_CH3{slash}SDIO_D4-Pad139)") (class "Default")
      (node (ref "stm32f103zet6") (pin "139") (pinfunction "PB8/TIM4_CH3/SDIO_D4_139") (pintype "passive"))
    )
    (net (code "86") (name "unconnected-(stm32f103zet6-PB9{slash}TIM4_CH4{slash}SDIO_D5-Pad140)") (class "Default")
      (node (ref "stm32f103zet6") (pin "140") (pinfunction "PB9/TIM4_CH4/SDIO_D5_140") (pintype "passive"))
    )
    (net (code "87") (name "unconnected-(stm32f103zet6-PC4{slash}ADC12_IN14-Pad44)") (class "Default")
      (node (ref "stm32f103zet6") (pin "44") (pinfunction "PC4/ADC12_IN14_44") (pintype "passive"))
    )
    (net (code "88") (name "unconnected-(stm32f103zet6-PC5{slash}ADC12_IN15-Pad45)") (class "Default")
      (node (ref "stm32f103zet6") (pin "45") (pinfunction "PC5/ADC12_IN15_45") (pintype "passive"))
    )
    (net (code "89") (name "unconnected-(stm32f103zet6-PC6{slash}I2S2_MCK{slash}TIM8_CH1{slash}SDIO_D6-Pad96)") (class "Default")
      (node (ref "stm32f103zet6") (pin "96") (pinfunction "PC6/I2S2_MCK/TIM8_CH1/SDIO_D6_96") (pintype "passive"))
    )
    (net (code "90") (name "unconnected-(stm32f103zet6-PC7{slash}I2S3_MCK{slash}TIM8_CH2{slash}SDIO_D7-Pad97)") (class "Default")
      (node (ref "stm32f103zet6") (pin "97") (pinfunction "PC7/I2S3_MCK/TIM8_CH2/SDIO_D7_97") (pintype "passive"))
    )
    (net (code "91") (name "unconnected-(stm32f103zet6-PC8{slash}TIM8_CH3{slash}SDIO_D0-Pad98)") (class "Default")
      (node (ref "stm32f103zet6") (pin "98") (pinfunction "PC8/TIM8_CH3/SDIO_D0_98") (pintype "passive"))
    )
    (net (code "92") (name "unconnected-(stm32f103zet6-PC9{slash}TIM8_CH4{slash}SDIO_D1-Pad99)") (class "Default")
      (node (ref "stm32f103zet6") (pin "99") (pinfunction "PC9/TIM8_CH4/SDIO_D1_99") (pintype "passive"))
    )
    (net (code "93") (name "unconnected-(stm32f103zet6-PC13-TAMPER-RTC-Pad7)") (class "Default")
      (node (ref "stm32f103zet6") (pin "7") (pinfunction "PC13-TAMPER-RTC_7") (pintype "passive"))
    )
    (net (code "94") (name "unconnected-(stm32f103zet6-PD0{slash}FSMC_D2-Pad114)") (class "Default")
      (node (ref "stm32f103zet6") (pin "114") (pinfunction "PD0/FSMC_D2_114") (pintype "passive"))
    )
    (net (code "95") (name "unconnected-(stm32f103zet6-PD1{slash}FSMC_D3-Pad115)") (class "Default")
      (node (ref "stm32f103zet6") (pin "115") (pinfunction "PD1/FSMC_D3_115") (pintype "passive"))
    )
    (net (code "96") (name "unconnected-(stm32f103zet6-PD5{slash}FSMC_NWE-Pad119)") (class "Default")
      (node (ref "stm32f103zet6") (pin "119") (pinfunction "PD5/FSMC_NWE_119") (pintype "passive"))
    )
    (net (code "97") (name "unconnected-(stm32f103zet6-PD8{slash}FSMC_D13-Pad77)") (class "Default")
      (node (ref "stm32f103zet6") (pin "77") (pinfunction "PD8/FSMC_D13_77") (pintype "passive"))
    )
    (net (code "98") (name "unconnected-(stm32f103zet6-PD9{slash}FSMC_D14-Pad78)") (class "Default")
      (node (ref "stm32f103zet6") (pin "78") (pinfunction "PD9/FSMC_D14_78") (pintype "passive"))
    )
    (net (code "99") (name "unconnected-(stm32f103zet6-PD10{slash}FSMC_D15-Pad79)") (class "Default")
      (node (ref "stm32f103zet6") (pin "79") (pinfunction "PD10/FSMC_D15_79") (pintype "passive"))
    )
    (net (code "100") (name "unconnected-(stm32f103zet6-PD11{slash}FSMC_A16-Pad80)") (class "Default")
      (node (ref "stm32f103zet6") (pin "80") (pinfunction "PD11/FSMC_A16_80") (pintype "passive"))
    )
    (net (code "101") (name "unconnected-(stm32f103zet6-PD12{slash}FSMC_A17-Pad81)") (class "Default")
      (node (ref "stm32f103zet6") (pin "81") (pinfunction "PD12/FSMC_A17_81") (pintype "passive"))
    )
    (net (code "102") (name "unconnected-(stm32f103zet6-PD13{slash}FSMC_A18-Pad82)") (class "Default")
      (node (ref "stm32f103zet6") (pin "82") (pinfunction "PD13/FSMC_A18_82") (pintype "passive"))
    )
    (net (code "103") (name "unconnected-(stm32f103zet6-PD14{slash}FSMC_D0-Pad85)") (class "Default")
      (node (ref "stm32f103zet6") (pin "85") (pinfunction "PD14/FSMC_D0_85") (pintype "passive"))
    )
    (net (code "104") (name "unconnected-(stm32f103zet6-PD15{slash}FSMC_D1-Pad86)") (class "Default")
      (node (ref "stm32f103zet6") (pin "86") (pinfunction "PD15/FSMC_D1_86") (pintype "passive"))
    )
    (net (code "105") (name "unconnected-(stm32f103zet6-PE0{slash}TIM4_ETR{slash}FSMC_NBL0-Pad141)") (class "Default")
      (node (ref "stm32f103zet6") (pin "141") (pinfunction "PE0/TIM4_ETR/FSMC_NBL0_141") (pintype "passive"))
    )
    (net (code "106") (name "unconnected-(stm32f103zet6-PE1{slash}FSMC_NBL1-Pad142)") (class "Default")
      (node (ref "stm32f103zet6") (pin "142") (pinfunction "PE1/FSMC_NBL1_142") (pintype "passive"))
    )
    (net (code "107") (name "unconnected-(stm32f103zet6-PE6{slash}TRACED3{slash}FSMC_A22-Pad5)") (class "Default")
      (node (ref "stm32f103zet6") (pin "5") (pinfunction "PE6/TRACED3/FSMC_A22_5") (pintype "passive"))
    )
    (net (code "108") (name "unconnected-(stm32f103zet6-PE10{slash}FSMC_D7-Pad63)") (class "Default")
      (node (ref "stm32f103zet6") (pin "63") (pinfunction "PE10/FSMC_D7_63") (pintype "passive"))
    )
    (net (code "109") (name "unconnected-(stm32f103zet6-PE11{slash}FSMC_D8-Pad64)") (class "Default")
      (node (ref "stm32f103zet6") (pin "64") (pinfunction "PE11/FSMC_D8_64") (pintype "passive"))
    )
    (net (code "110") (name "unconnected-(stm32f103zet6-PE12{slash}FSMC_D9-Pad65)") (class "Default")
      (node (ref "stm32f103zet6") (pin "65") (pinfunction "PE12/FSMC_D9_65") (pintype "passive"))
    )
    (net (code "111") (name "unconnected-(stm32f103zet6-PE13{slash}FSMC_D10-Pad66)") (class "Default")
      (node (ref "stm32f103zet6") (pin "66") (pinfunction "PE13/FSMC_D10_66") (pintype "passive"))
    )
    (net (code "112") (name "unconnected-(stm32f103zet6-PE14{slash}FSMC_D11-Pad67)") (class "Default")
      (node (ref "stm32f103zet6") (pin "67") (pinfunction "PE14/FSMC_D11_67") (pintype "passive"))
    )
    (net (code "113") (name "unconnected-(stm32f103zet6-PE15{slash}FSMC_D12-Pad68)") (class "Default")
      (node (ref "stm32f103zet6") (pin "68") (pinfunction "PE15/FSMC_D12_68") (pintype "passive"))
    )
    (net (code "114") (name "unconnected-(stm32f103zet6-PF0{slash}FSMC_A0-Pad10)") (class "Default")
      (node (ref "stm32f103zet6") (pin "10") (pinfunction "PF0/FSMC_A0_10") (pintype "passive"))
    )
    (net (code "115") (name "unconnected-(stm32f103zet6-PF1{slash}FSMC_A1-Pad11)") (class "Default")
      (node (ref "stm32f103zet6") (pin "11") (pinfunction "PF1/FSMC_A1_11") (pintype "passive"))
    )
    (net (code "116") (name "unconnected-(stm32f103zet6-PF2{slash}FSMC_A2-Pad12)") (class "Default")
      (node (ref "stm32f103zet6") (pin "12") (pinfunction "PF2/FSMC_A2_12") (pintype "passive"))
    )
    (net (code "117") (name "unconnected-(stm32f103zet6-PF3{slash}FSMC_A3-Pad13)") (class "Default")
      (node (ref "stm32f103zet6") (pin "13") (pinfunction "PF3/FSMC_A3_13") (pintype "passive"))
    )
    (net (code "118") (name "unconnected-(stm32f103zet6-PF4{slash}FSMC_A4-Pad14)") (class "Default")
      (node (ref "stm32f103zet6") (pin "14") (pinfunction "PF4/FSMC_A4_14") (pintype "passive"))
    )
    (net (code "119") (name "unconnected-(stm32f103zet6-PF5{slash}FSMC_A5-Pad15)") (class "Default")
      (node (ref "stm32f103zet6") (pin "15") (pinfunction "PF5/FSMC_A5_15") (pintype "passive"))
    )
    (net (code "120") (name "unconnected-(stm32f103zet6-PF6{slash}ADC3_IN4{slash}FSMC_NIORD-Pad18)") (class "Default")
      (node (ref "stm32f103zet6") (pin "18") (pinfunction "PF6/ADC3_IN4/FSMC_NIORD_18") (pintype "passive"))
    )
    (net (code "121") (name "unconnected-(stm32f103zet6-PF7{slash}ADC3_IN5{slash}FSMC_NREG-Pad19)") (class "Default")
      (node (ref "stm32f103zet6") (pin "19") (pinfunction "PF7/ADC3_IN5/FSMC_NREG_19") (pintype "passive"))
    )
    (net (code "122") (name "unconnected-(stm32f103zet6-PF8{slash}ADC3_IN6{slash}FSMC_NIOWR-Pad20)") (class "Default")
      (node (ref "stm32f103zet6") (pin "20") (pinfunction "PF8/ADC3_IN6/FSMC_NIOWR_20") (pintype "passive"))
    )
    (net (code "123") (name "unconnected-(stm32f103zet6-PF9{slash}ADC3_IN7{slash}FSMC_CD-Pad21)") (class "Default")
      (node (ref "stm32f103zet6") (pin "21") (pinfunction "PF9/ADC3_IN7/FSMC_CD_21") (pintype "passive"))
    )
    (net (code "124") (name "unconnected-(stm32f103zet6-PF10{slash}ADC3_IN8{slash}FSMC_INTR-Pad22)") (class "Default")
      (node (ref "stm32f103zet6") (pin "22") (pinfunction "PF10/ADC3_IN8/FSMC_INTR_22") (pintype "passive"))
    )
    (net (code "125") (name "unconnected-(stm32f103zet6-PF11{slash}FSMC_NIOS16-Pad49)") (class "Default")
      (node (ref "stm32f103zet6") (pin "49") (pinfunction "PF11/FSMC_NIOS16_49") (pintype "passive"))
    )
    (net (code "126") (name "unconnected-(stm32f103zet6-PF12{slash}FSMC_A6-Pad50)") (class "Default")
      (node (ref "stm32f103zet6") (pin "50") (pinfunction "PF12/FSMC_A6_50") (pintype "passive"))
    )
    (net (code "127") (name "unconnected-(stm32f103zet6-PG2{slash}FSMC_A12-Pad87)") (class "Default")
      (node (ref "stm32f103zet6") (pin "87") (pinfunction "PG2/FSMC_A12_87") (pintype "passive"))
    )
    (net (code "128") (name "unconnected-(stm32f103zet6-PG3{slash}FSMC_A13-Pad88)") (class "Default")
      (node (ref "stm32f103zet6") (pin "88") (pinfunction "PG3/FSMC_A13_88") (pintype "passive"))
    )
    (net (code "129") (name "unconnected-(stm32f103zet6-PG4{slash}FSMC_A14-Pad89)") (class "Default")
      (node (ref "stm32f103zet6") (pin "89") (pinfunction "PG4/FSMC_A14_89") (pintype "passive"))
    )
    (net (code "130") (name "unconnected-(stm32f103zet6-PG5{slash}FSMC_A15-Pad90)") (class "Default")
      (node (ref "stm32f103zet6") (pin "90") (pinfunction "PG5/FSMC_A15_90") (pintype "passive"))
    )
    (net (code "131") (name "unconnected-(stm32f103zet6-PG6{slash}FSMC_INT2-Pad91)") (class "Default")
      (node (ref "stm32f103zet6") (pin "91") (pinfunction "PG6/FSMC_INT2_91") (pintype "passive"))
    )
    (net (code "132") (name "unconnected-(stm32f103zet6-PG7{slash}FSMC_INT3-Pad92)") (class "Default")
      (node (ref "stm32f103zet6") (pin "92") (pinfunction "PG7/FSMC_INT3_92") (pintype "passive"))
    )
    (net (code "133") (name "unconnected-(stm32f103zet6-PG8-Pad93)") (class "Default")
      (node (ref "stm32f103zet6") (pin "93") (pinfunction "PG8_93") (pintype "passive"))
    )
    (net (code "134") (name "unconnected-(stm32f103zet6-PG15-Pad132)") (class "Default")
      (node (ref "stm32f103zet6") (pin "132") (pinfunction "PG15_132") (pintype "passive"))
    )
    (net (code "135") (name "unconnected-(stm32f103zet6-VBAT-Pad6)") (class "Default")
      (node (ref "stm32f103zet6") (pin "6") (pinfunction "VBAT_6") (pintype "passive+no_connect"))
    )
  )
)
